# M2.net
KiCad netlist of a schematic drawn in EAGLE
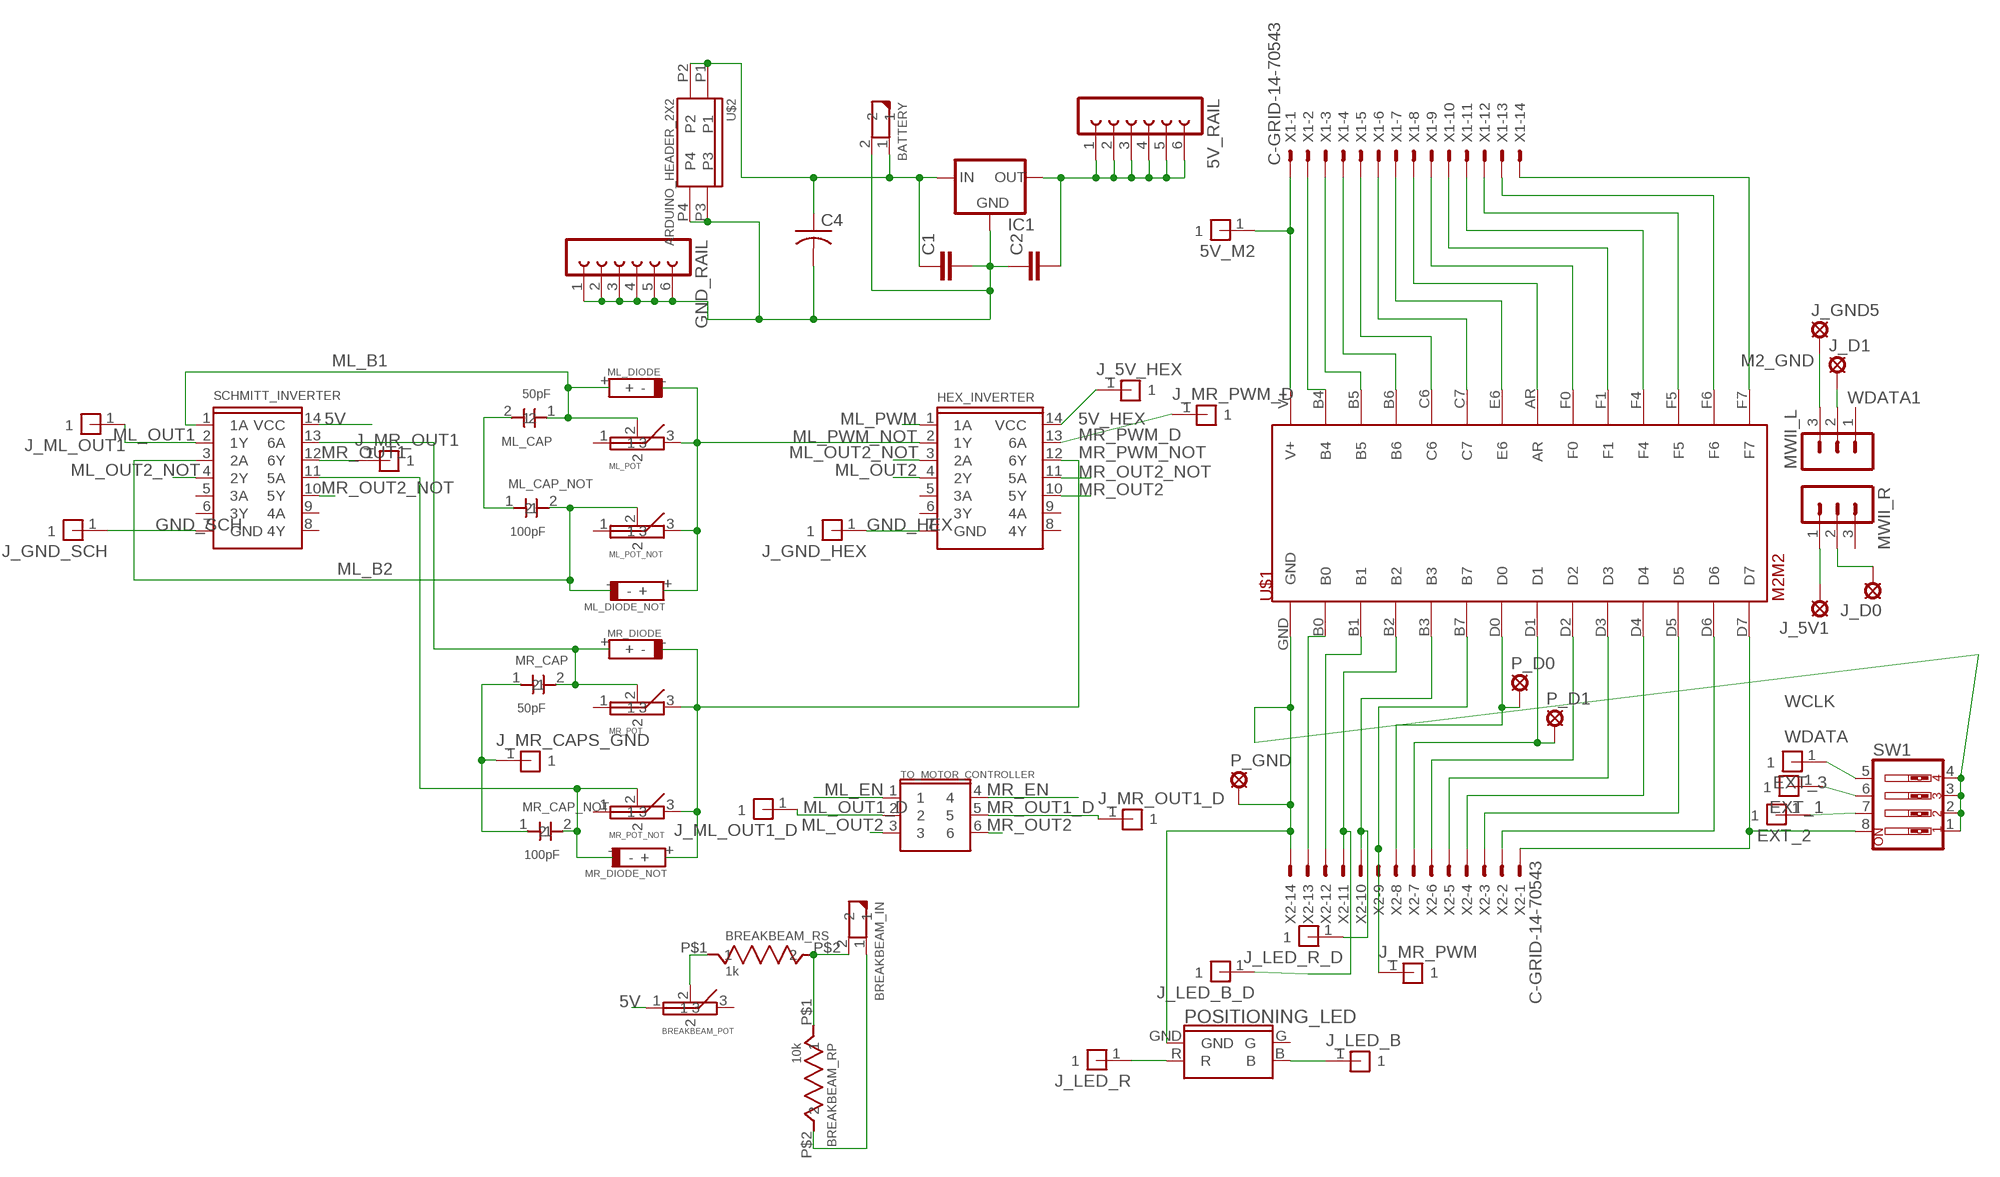
[diagram p0: schematic, sheet 1]

(export (version "E")
  (design (tool "Eeschema 10.0.6"))
  (components
    (comp (ref "5V_M2")
      (value "ARDUINO_HEADER_1X1_OCTAGON")
      (footprint "eagle-import:ARDUINO_HEADER_1X1_OCTAGON")
      (libsource (lib "eagle-import") (part "ARDUINO_HEADER_1X1_OCTAGON"))
    )
    (comp (ref "5V_RAIL")
      (value "FE06-1")
      (footprint "eagle-import:FE06")
      (libsource (lib "eagle-import") (part "FE06-1"))
    )
    (comp (ref "BATTERY")
      (value "MOLEX_2_PIN")
      (footprint "eagle-import:MOLEX_2_PIN")
      (libsource (lib "eagle-import") (part "MOLEX_2_PIN"))
    )
    (comp (ref "BREAKBEAM_IN")
      (value "MOLEX_2_PIN")
      (footprint "eagle-import:MOLEX_2_PIN")
      (libsource (lib "eagle-import") (part "MOLEX_2_PIN"))
    )
    (comp (ref "BREAKBEAM_POT")
      (value "POTENTIOMETER_1")
      (footprint "eagle-import:POTENTIOMETER_1")
      (libsource (lib "eagle-import") (part "POTENTIOMETER_1"))
    )
    (comp (ref "BREAKBEAM_RP")
      (value "10k")
      (footprint "eagle-import:RESISTOR_THROUGH_8MM")
      (libsource (lib "eagle-import") (part "RESISTOR_THROUGH_8MM"))
    )
    (comp (ref "BREAKBEAM_RS")
      (value "1k")
      (footprint "eagle-import:RESISTOR_THROUGH_8MM")
      (libsource (lib "eagle-import") (part "RESISTOR_THROUGH_8MM"))
    )
    (comp (ref "C1")
      (value "C2,5-3")
      (footprint "eagle-import:C2.5-3")
      (libsource (lib "eagle-import") (part "C2,5-3"))
    )
    (comp (ref "C2")
      (value "C2,5-3")
      (footprint "eagle-import:C2.5-3")
      (libsource (lib "eagle-import") (part "C2,5-3"))
    )
    (comp (ref "C4")
      (value "C-US050-025X075")
      (footprint "eagle-import:C050-025X075")
      (libsource (lib "eagle-import") (part "C-US050-025X075"))
    )
    (comp (ref "EXT_1")
      (value "ARDUINO_HEADER_1X1_OCTAGON")
      (footprint "eagle-import:ARDUINO_HEADER_1X1_OCTAGON")
      (libsource (lib "eagle-import") (part "ARDUINO_HEADER_1X1_OCTAGON"))
    )
    (comp (ref "EXT_2")
      (value "ARDUINO_HEADER_1X1_OCTAGON")
      (footprint "eagle-import:ARDUINO_HEADER_1X1_OCTAGON")
      (libsource (lib "eagle-import") (part "ARDUINO_HEADER_1X1_OCTAGON"))
    )
    (comp (ref "EXT_3")
      (value "ARDUINO_HEADER_1X1_OCTAGON")
      (footprint "eagle-import:ARDUINO_HEADER_1X1_OCTAGON")
      (libsource (lib "eagle-import") (part "ARDUINO_HEADER_1X1_OCTAGON"))
    )
    (comp (ref "GND_RAIL")
      (value "FE06-1")
      (footprint "eagle-import:FE06")
      (libsource (lib "eagle-import") (part "FE06-1"))
    )
    (comp (ref "HEX_INVERTER")
      (value "SN74HC04N_HEX_INVERTER")
      (footprint "eagle-import:DIP14")
      (libsource (lib "eagle-import") (part "SN74HC04N_HEX_INVERTER"))
    )
    (comp (ref "IC1")
      (value "78MXXS")
      (footprint "eagle-import:78MXXS")
      (libsource (lib "eagle-import") (part "78MXXS"))
    )
    (comp (ref "J_5V1")
      (value "LSP10")
      (footprint "eagle-import:LSP10")
      (libsource (lib "eagle-import") (part "LSP10"))
    )
    (comp (ref "J_5V_HEX")
      (value "ARDUINO_HEADER_1X1_OCTAGON")
      (footprint "eagle-import:ARDUINO_HEADER_1X1_OCTAGON")
      (libsource (lib "eagle-import") (part "ARDUINO_HEADER_1X1_OCTAGON"))
    )
    (comp (ref "J_D0")
      (value "LSP10")
      (footprint "eagle-import:LSP10")
      (libsource (lib "eagle-import") (part "LSP10"))
    )
    (comp (ref "J_D1")
      (value "LSP10")
      (footprint "eagle-import:LSP10")
      (libsource (lib "eagle-import") (part "LSP10"))
    )
    (comp (ref "J_GND5")
      (value "LSP10")
      (footprint "eagle-import:LSP10")
      (libsource (lib "eagle-import") (part "LSP10"))
    )
    (comp (ref "J_GND_HEX")
      (value "ARDUINO_HEADER_1X1_OCTAGON")
      (footprint "eagle-import:ARDUINO_HEADER_1X1_OCTAGON")
      (libsource (lib "eagle-import") (part "ARDUINO_HEADER_1X1_OCTAGON"))
    )
    (comp (ref "J_GND_SCH")
      (value "ARDUINO_HEADER_1X1_OCTAGON")
      (footprint "eagle-import:ARDUINO_HEADER_1X1_OCTAGON")
      (libsource (lib "eagle-import") (part "ARDUINO_HEADER_1X1_OCTAGON"))
    )
    (comp (ref "J_LED_B")
      (value "ARDUINO_HEADER_1X1_OCTAGON")
      (footprint "eagle-import:ARDUINO_HEADER_1X1_OCTAGON")
      (libsource (lib "eagle-import") (part "ARDUINO_HEADER_1X1_OCTAGON"))
    )
    (comp (ref "J_LED_B_D")
      (value "ARDUINO_HEADER_1X1_OCTAGON")
      (footprint "eagle-import:ARDUINO_HEADER_1X1_OCTAGON")
      (libsource (lib "eagle-import") (part "ARDUINO_HEADER_1X1_OCTAGON"))
    )
    (comp (ref "J_LED_R")
      (value "ARDUINO_HEADER_1X1_OCTAGON")
      (footprint "eagle-import:ARDUINO_HEADER_1X1_OCTAGON")
      (libsource (lib "eagle-import") (part "ARDUINO_HEADER_1X1_OCTAGON"))
    )
    (comp (ref "J_LED_R_D")
      (value "ARDUINO_HEADER_1X1_OCTAGON")
      (footprint "eagle-import:ARDUINO_HEADER_1X1_OCTAGON")
      (libsource (lib "eagle-import") (part "ARDUINO_HEADER_1X1_OCTAGON"))
    )
    (comp (ref "J_ML_OUT1")
      (value "ARDUINO_HEADER_1X1_OCTAGON")
      (footprint "eagle-import:ARDUINO_HEADER_1X1_OCTAGON")
      (libsource (lib "eagle-import") (part "ARDUINO_HEADER_1X1_OCTAGON"))
    )
    (comp (ref "J_ML_OUT1_D")
      (value "ARDUINO_HEADER_1X1_OCTAGON")
      (footprint "eagle-import:ARDUINO_HEADER_1X1_OCTAGON")
      (libsource (lib "eagle-import") (part "ARDUINO_HEADER_1X1_OCTAGON"))
    )
    (comp (ref "J_MR_CAPS_GND")
      (value "ARDUINO_HEADER_1X1_OCTAGON")
      (footprint "eagle-import:ARDUINO_HEADER_1X1_OCTAGON")
      (libsource (lib "eagle-import") (part "ARDUINO_HEADER_1X1_OCTAGON"))
    )
    (comp (ref "J_MR_OUT1")
      (value "ARDUINO_HEADER_1X1_OCTAGON")
      (footprint "eagle-import:ARDUINO_HEADER_1X1_OCTAGON")
      (libsource (lib "eagle-import") (part "ARDUINO_HEADER_1X1_OCTAGON"))
    )
    (comp (ref "J_MR_OUT1_D")
      (value "ARDUINO_HEADER_1X1_OCTAGON")
      (footprint "eagle-import:ARDUINO_HEADER_1X1_OCTAGON")
      (libsource (lib "eagle-import") (part "ARDUINO_HEADER_1X1_OCTAGON"))
    )
    (comp (ref "J_MR_PWM")
      (value "ARDUINO_HEADER_1X1_OCTAGON")
      (footprint "eagle-import:ARDUINO_HEADER_1X1_OCTAGON")
      (libsource (lib "eagle-import") (part "ARDUINO_HEADER_1X1_OCTAGON"))
    )
    (comp (ref "J_MR_PWM_D")
      (value "ARDUINO_HEADER_1X1_OCTAGON")
      (footprint "eagle-import:ARDUINO_HEADER_1X1_OCTAGON")
      (libsource (lib "eagle-import") (part "ARDUINO_HEADER_1X1_OCTAGON"))
    )
    (comp (ref "ML_CAP")
      (value "50pF")
      (footprint "eagle-import:CERAMIC_CAPACITOR")
      (libsource (lib "eagle-import") (part "CERAMIC_CAPACITOR"))
    )
    (comp (ref "ML_CAP_NOT")
      (value "100pF")
      (footprint "eagle-import:CERAMIC_CAPACITOR")
      (libsource (lib "eagle-import") (part "CERAMIC_CAPACITOR"))
    )
    (comp (ref "ML_DIODE")
      (value "1N914B")
      (footprint "eagle-import:1N914B")
      (libsource (lib "eagle-import") (part "1N914B"))
    )
    (comp (ref "ML_DIODE_NOT")
      (value "1N914B")
      (footprint "eagle-import:1N914B")
      (libsource (lib "eagle-import") (part "1N914B"))
    )
    (comp (ref "ML_POT")
      (value "POTENTIOMETER_1")
      (footprint "eagle-import:POTENTIOMETER_1")
      (libsource (lib "eagle-import") (part "POTENTIOMETER_1"))
    )
    (comp (ref "ML_POT_NOT")
      (value "POTENTIOMETER_1")
      (footprint "eagle-import:POTENTIOMETER_1")
      (libsource (lib "eagle-import") (part "POTENTIOMETER_1"))
    )
    (comp (ref "MR_CAP")
      (value "50pF")
      (footprint "eagle-import:CERAMIC_CAPACITOR")
      (libsource (lib "eagle-import") (part "CERAMIC_CAPACITOR"))
    )
    (comp (ref "MR_CAP_NOT")
      (value "100pF")
      (footprint "eagle-import:CERAMIC_CAPACITOR")
      (libsource (lib "eagle-import") (part "CERAMIC_CAPACITOR"))
    )
    (comp (ref "MR_DIODE")
      (value "1N914B")
      (footprint "eagle-import:1N914B")
      (libsource (lib "eagle-import") (part "1N914B"))
    )
    (comp (ref "MR_DIODE_NOT")
      (value "1N914B")
      (footprint "eagle-import:1N914B")
      (libsource (lib "eagle-import") (part "1N914B"))
    )
    (comp (ref "MR_POT")
      (value "POTENTIOMETER_1")
      (footprint "eagle-import:POTENTIOMETER_1")
      (libsource (lib "eagle-import") (part "POTENTIOMETER_1"))
    )
    (comp (ref "MR_POT_NOT")
      (value "POTENTIOMETER_1")
      (footprint "eagle-import:POTENTIOMETER_1")
      (libsource (lib "eagle-import") (part "POTENTIOMETER_1"))
    )
    (comp (ref "MWII_L")
      (value "MA03-1")
      (footprint "eagle-import:MA03-1")
      (libsource (lib "eagle-import") (part "MA03-1"))
    )
    (comp (ref "MWII_R")
      (value "MA03-1")
      (footprint "eagle-import:MA03-1")
      (libsource (lib "eagle-import") (part "MA03-1"))
    )
    (comp (ref "POSITIONING_LED")
      (value "RGB_LED")
      (footprint "eagle-import:RBG_LED")
      (libsource (lib "eagle-import") (part "RGB_LED"))
    )
    (comp (ref "P_D0")
      (value "LSP10")
      (footprint "eagle-import:LSP10")
      (libsource (lib "eagle-import") (part "LSP10"))
    )
    (comp (ref "P_D1")
      (value "LSP10")
      (footprint "eagle-import:LSP10")
      (libsource (lib "eagle-import") (part "LSP10"))
    )
    (comp (ref "P_GND")
      (value "LSP10")
      (footprint "eagle-import:LSP10")
      (libsource (lib "eagle-import") (part "LSP10"))
    )
    (comp (ref "SCHMITT_INVERTER")
      (value "SN74HC14N_SCHMITT_INVERTER")
      (footprint "eagle-import:DIP14")
      (libsource (lib "eagle-import") (part "SN74HC14N_SCHMITT_INVERTER"))
    )
    (comp (ref "SW1")
      (value "SW_DIP-4")
      (footprint "eagle-import:EDG-04")
      (libsource (lib "eagle-import") (part "SW_DIP-4"))
    )
    (comp (ref "TO_MOTOR_CONTROLLER")
      (value "ARDUINO_HEADER_3X2")
      (footprint "eagle-import:ARDUINO_HEADER_3X2")
      (libsource (lib "eagle-import") (part "ARDUINO_HEADER_3X2"))
    )
    (comp (ref "U$1")
      (value "M2M2")
      (footprint "eagle-import:M2")
      (libsource (lib "eagle-import") (part "M2M2"))
    )
    (comp (ref "U$2")
      (value "ARDUINO_HEADER_2X2")
      (footprint "eagle-import:ARDUINO_HEADER_2X2")
      (libsource (lib "eagle-import") (part "ARDUINO_HEADER_2X2"))
    )
    (comp (ref "X1")
      (value "C-GRID-14-70543")
      (footprint "eagle-import:70543-14")
      (libsource (lib "eagle-import") (part "C-GRID-14-70543"))
    )
    (comp (ref "X2")
      (value "C-GRID-14-70543")
      (footprint "eagle-import:70543-14")
      (libsource (lib "eagle-import") (part "C-GRID-14-70543"))
    )
  )
  (nets
    (net (code "1") (name "/5V") (class "Default")
      (node (ref "5V_RAIL") (pin "1") (pinfunction "1_1") (pintype "passive"))
      (node (ref "5V_RAIL") (pin "2") (pinfunction "2_2") (pintype "passive"))
      (node (ref "5V_RAIL") (pin "3") (pinfunction "3_3") (pintype "passive"))
      (node (ref "5V_RAIL") (pin "4") (pinfunction "4_4") (pintype "passive"))
      (node (ref "5V_RAIL") (pin "5") (pinfunction "5_5") (pintype "passive"))
      (node (ref "5V_RAIL") (pin "6") (pinfunction "6_6") (pintype "passive"))
      (node (ref "BREAKBEAM_POT") (pin "1") (pinfunction "1_1") (pintype "bidirectional"))
      (node (ref "C2") (pin "2") (pinfunction "2_2") (pintype "passive"))
      (node (ref "IC1") (pin "OUT") (pinfunction "OUT_OUT") (pintype "passive"))
      (node (ref "SCHMITT_INVERTER") (pin "14") (pinfunction "VCC_14") (pintype "bidirectional"))
    )
    (net (code "2") (name "/5V_HEX") (class "Default")
      (node (ref "HEX_INVERTER") (pin "14") (pinfunction "VCC_14") (pintype "bidirectional"))
      (node (ref "J_5V_HEX") (pin "1") (pinfunction "1_1") (pintype "bidirectional"))
    )
    (net (code "3") (name "/BREAKBEAM_OUT") (class "Default")
      (node (ref "BREAKBEAM_IN") (pin "2") (pinfunction "2_2") (pintype "bidirectional"))
      (node (ref "BREAKBEAM_RP") (pin "P$1") (pinfunction "1_P$1") (pintype "bidirectional"))
      (node (ref "BREAKBEAM_RS") (pin "P$2") (pinfunction "2_P$2") (pintype "bidirectional"))
      (node (ref "U$1") (pin "C6") (pinfunction "C6_C6") (pintype "bidirectional"))
      (node (ref "X1") (pin "5") (pinfunction "S_5") (pintype "passive"))
    )
    (net (code "4") (name "/GND_HEX") (class "Default")
      (node (ref "HEX_INVERTER") (pin "7") (pinfunction "GND_7") (pintype "bidirectional"))
      (node (ref "J_GND_HEX") (pin "1") (pinfunction "1_1") (pintype "bidirectional"))
    )
    (net (code "5") (name "/GND_SCH") (class "Default")
      (node (ref "J_GND_SCH") (pin "1") (pinfunction "1_1") (pintype "bidirectional"))
      (node (ref "SCHMITT_INVERTER") (pin "7") (pinfunction "GND_7") (pintype "bidirectional"))
    )
    (net (code "6") (name "/M2_GND") (class "Default")
      (node (ref "BREAKBEAM_IN") (pin "1") (pinfunction "1_1") (pintype "bidirectional"))
      (node (ref "BREAKBEAM_RP") (pin "P$2") (pinfunction "2_P$2") (pintype "bidirectional"))
      (node (ref "J_GND5") (pin "MP") (pinfunction "MP_MP") (pintype "passive"))
      (node (ref "MWII_L") (pin "3") (pinfunction "3_3") (pintype "passive"))
    )
    (net (code "7") (name "/ML_B1") (class "Default")
      (node (ref "ML_CAP") (pin "1") (pinfunction "1_1") (pintype "bidirectional"))
      (node (ref "ML_DIODE") (pin "+") (pinfunction "+_+") (pintype "input"))
      (node (ref "ML_POT") (pin "2") (pinfunction "2_2") (pintype "bidirectional"))
      (node (ref "SCHMITT_INVERTER") (pin "1") (pinfunction "1A_1") (pintype "bidirectional"))
    )
    (net (code "8") (name "/ML_B2") (class "Default")
      (node (ref "ML_CAP_NOT") (pin "2") (pinfunction "2_2") (pintype "bidirectional"))
      (node (ref "ML_DIODE_NOT") (pin "-") (pinfunction "-_-") (pintype "output"))
      (node (ref "ML_POT_NOT") (pin "2") (pinfunction "2_2") (pintype "bidirectional"))
      (node (ref "SCHMITT_INVERTER") (pin "3") (pinfunction "2A_3") (pintype "bidirectional"))
    )
    (net (code "9") (name "/ML_EN") (class "Default")
      (node (ref "TO_MOTOR_CONTROLLER") (pin "1") (pinfunction "1_1") (pintype "bidirectional"))
      (node (ref "U$1") (pin "B0") (pinfunction "B0_B0") (pintype "bidirectional"))
      (node (ref "X2") (pin "13") (pinfunction "S_13") (pintype "passive"))
    )
    (net (code "10") (name "/ML_OUT1") (class "Default")
      (node (ref "J_ML_OUT1") (pin "1") (pinfunction "1_1") (pintype "bidirectional"))
      (node (ref "SCHMITT_INVERTER") (pin "2") (pinfunction "1Y_2") (pintype "bidirectional"))
    )
    (net (code "11") (name "/ML_OUT1_D") (class "Default")
      (node (ref "J_ML_OUT1_D") (pin "1") (pinfunction "1_1") (pintype "bidirectional"))
      (node (ref "TO_MOTOR_CONTROLLER") (pin "2") (pinfunction "2_2") (pintype "bidirectional"))
    )
    (net (code "12") (name "/ML_OUT2") (class "Default")
      (node (ref "HEX_INVERTER") (pin "4") (pinfunction "2Y_4") (pintype "bidirectional"))
      (node (ref "TO_MOTOR_CONTROLLER") (pin "3") (pinfunction "3_3") (pintype "bidirectional"))
    )
    (net (code "13") (name "/ML_OUT2_NOT") (class "Default")
      (node (ref "HEX_INVERTER") (pin "3") (pinfunction "2A_3") (pintype "bidirectional"))
      (node (ref "SCHMITT_INVERTER") (pin "4") (pinfunction "2Y_4") (pintype "bidirectional"))
    )
    (net (code "14") (name "/ML_PWM") (class "Default")
      (node (ref "HEX_INVERTER") (pin "1") (pinfunction "1A_1") (pintype "bidirectional"))
      (node (ref "U$1") (pin "B6") (pinfunction "B6_B6") (pintype "bidirectional"))
      (node (ref "X1") (pin "4") (pinfunction "S_4") (pintype "passive"))
    )
    (net (code "15") (name "/ML_PWM_NOT") (class "Default")
      (node (ref "HEX_INVERTER") (pin "2") (pinfunction "1Y_2") (pintype "bidirectional"))
      (node (ref "ML_DIODE") (pin "-") (pinfunction "-_-") (pintype "output"))
      (node (ref "ML_DIODE_NOT") (pin "+") (pinfunction "+_+") (pintype "input"))
      (node (ref "ML_POT") (pin "3") (pinfunction "3_3") (pintype "bidirectional"))
      (node (ref "ML_POT_NOT") (pin "3") (pinfunction "3_3") (pintype "bidirectional"))
    )
    (net (code "16") (name "/MR_EN") (class "Default")
      (node (ref "TO_MOTOR_CONTROLLER") (pin "4") (pinfunction "4_4") (pintype "bidirectional"))
      (node (ref "U$1") (pin "B1") (pinfunction "B1_B1") (pintype "bidirectional"))
      (node (ref "X2") (pin "12") (pinfunction "S_12") (pintype "passive"))
    )
    (net (code "17") (name "/MR_OUT1") (class "Default")
      (node (ref "J_MR_OUT1") (pin "1") (pinfunction "1_1") (pintype "bidirectional"))
      (node (ref "SCHMITT_INVERTER") (pin "12") (pinfunction "6Y_12") (pintype "bidirectional"))
    )
    (net (code "18") (name "/MR_OUT1_D") (class "Default")
      (node (ref "J_MR_OUT1_D") (pin "1") (pinfunction "1_1") (pintype "bidirectional"))
      (node (ref "TO_MOTOR_CONTROLLER") (pin "5") (pinfunction "5_5") (pintype "bidirectional"))
    )
    (net (code "19") (name "/MR_OUT2") (class "Default")
      (node (ref "HEX_INVERTER") (pin "10") (pinfunction "5Y_10") (pintype "bidirectional"))
      (node (ref "TO_MOTOR_CONTROLLER") (pin "6") (pinfunction "6_6") (pintype "bidirectional"))
    )
    (net (code "20") (name "/MR_OUT2_NOT") (class "Default")
      (node (ref "HEX_INVERTER") (pin "11") (pinfunction "5A_11") (pintype "bidirectional"))
      (node (ref "SCHMITT_INVERTER") (pin "10") (pinfunction "5Y_10") (pintype "bidirectional"))
    )
    (net (code "21") (name "/MR_PWM_D") (class "Default")
      (node (ref "HEX_INVERTER") (pin "13") (pinfunction "6A_13") (pintype "bidirectional"))
      (node (ref "J_MR_PWM_D") (pin "1") (pinfunction "1_1") (pintype "bidirectional"))
    )
    (net (code "22") (name "/MR_PWM_NOT") (class "Default")
      (node (ref "HEX_INVERTER") (pin "12") (pinfunction "6Y_12") (pintype "bidirectional"))
      (node (ref "MR_DIODE") (pin "-") (pinfunction "-_-") (pintype "output"))
      (node (ref "MR_DIODE_NOT") (pin "+") (pinfunction "+_+") (pintype "input"))
      (node (ref "MR_POT") (pin "3") (pinfunction "3_3") (pintype "bidirectional"))
      (node (ref "MR_POT_NOT") (pin "3") (pinfunction "3_3") (pintype "bidirectional"))
    )
    (net (code "23") (name "/WCLK") (class "Default")
      (node (ref "P_D0") (pin "MP") (pinfunction "MP_MP") (pintype "passive"))
      (node (ref "U$1") (pin "D0") (pinfunction "D0_D0") (pintype "bidirectional"))
      (node (ref "X2") (pin "8") (pinfunction "S_8") (pintype "passive"))
    )
    (net (code "24") (name "/WDATA") (class "Default")
      (node (ref "P_D1") (pin "MP") (pinfunction "MP_MP") (pintype "passive"))
      (node (ref "U$1") (pin "D1") (pinfunction "D1_D1") (pintype "bidirectional"))
      (node (ref "X2") (pin "7") (pinfunction "S_7") (pintype "passive"))
    )
    (net (code "25") (name "/WDATA1") (class "Default")
      (node (ref "J_D1") (pin "MP") (pinfunction "MP_MP") (pintype "passive"))
      (node (ref "MWII_L") (pin "2") (pinfunction "2_2") (pintype "passive"))
    )
    (net (code "26") (name "Net-(BATTERY-Pad1)") (class "Default")
      (node (ref "BATTERY") (pin "1") (pinfunction "1_1") (pintype "bidirectional"))
      (node (ref "C1") (pin "1") (pinfunction "1_1") (pintype "passive"))
      (node (ref "C4") (pin "1") (pinfunction "1_1") (pintype "passive"))
      (node (ref "IC1") (pin "IN") (pinfunction "IN_IN") (pintype "input"))
      (node (ref "U$2") (pin "P1") (pinfunction "P1_P1") (pintype "bidirectional"))
      (node (ref "U$2") (pin "P2") (pinfunction "P2_P2") (pintype "bidirectional"))
    )
    (net (code "27") (name "Net-(BATTERY-Pad2)") (class "Default")
      (node (ref "BATTERY") (pin "2") (pinfunction "2_2") (pintype "bidirectional"))
      (node (ref "C1") (pin "2") (pinfunction "2_2") (pintype "passive"))
      (node (ref "C2") (pin "1") (pinfunction "1_1") (pintype "passive"))
      (node (ref "C4") (pin "2") (pinfunction "2_2") (pintype "passive"))
      (node (ref "GND_RAIL") (pin "1") (pinfunction "1_1") (pintype "passive"))
      (node (ref "GND_RAIL") (pin "2") (pinfunction "2_2") (pintype "passive"))
      (node (ref "GND_RAIL") (pin "3") (pinfunction "3_3") (pintype "passive"))
      (node (ref "GND_RAIL") (pin "4") (pinfunction "4_4") (pintype "passive"))
      (node (ref "GND_RAIL") (pin "5") (pinfunction "5_5") (pintype "passive"))
      (node (ref "GND_RAIL") (pin "6") (pinfunction "6_6") (pintype "passive"))
      (node (ref "IC1") (pin "GND") (pinfunction "GND_GND") (pintype "input"))
      (node (ref "U$2") (pin "P3") (pinfunction "P3_P3") (pintype "bidirectional"))
      (node (ref "U$2") (pin "P4") (pinfunction "P4_P4") (pintype "bidirectional"))
    )
    (net (code "28") (name "Net-(BREAKBEAM_RS-1)") (class "Default")
      (node (ref "BREAKBEAM_POT") (pin "2") (pinfunction "2_2") (pintype "bidirectional"))
      (node (ref "BREAKBEAM_RS") (pin "P$1") (pinfunction "1_P$1") (pintype "bidirectional"))
    )
    (net (code "29") (name "Net-(EXT_1-Pad1)") (class "Default")
      (node (ref "EXT_1") (pin "1") (pinfunction "1_1") (pintype "bidirectional"))
      (node (ref "SW1") (pin "6") (pinfunction "6_6") (pintype "passive"))
    )
    (net (code "30") (name "Net-(EXT_2-Pad1)") (class "Default")
      (node (ref "EXT_2") (pin "1") (pinfunction "1_1") (pintype "bidirectional"))
      (node (ref "SW1") (pin "7") (pinfunction "7_7") (pintype "passive"))
    )
    (net (code "31") (name "Net-(EXT_3-Pad1)") (class "Default")
      (node (ref "EXT_3") (pin "1") (pinfunction "1_1") (pintype "bidirectional"))
      (node (ref "SW1") (pin "5") (pinfunction "5_5") (pintype "passive"))
    )
    (net (code "32") (name "Net-(J_5V1-PadMP)") (class "Default")
      (node (ref "J_5V1") (pin "MP") (pinfunction "MP_MP") (pintype "passive"))
      (node (ref "MWII_R") (pin "1") (pinfunction "1_1") (pintype "passive"))
    )
    (net (code "33") (name "Net-(J_D0-PadMP)") (class "Default")
      (node (ref "J_D0") (pin "MP") (pinfunction "MP_MP") (pintype "passive"))
      (node (ref "MWII_R") (pin "2") (pinfunction "2_2") (pintype "passive"))
    )
    (net (code "34") (name "Net-(J_LED_B-Pad1)") (class "Default")
      (node (ref "J_LED_B") (pin "1") (pinfunction "1_1") (pintype "bidirectional"))
      (node (ref "POSITIONING_LED") (pin "B") (pinfunction "B_B") (pintype "bidirectional"))
    )
    (net (code "35") (name "Net-(J_LED_R-Pad1)") (class "Default")
      (node (ref "J_LED_R") (pin "1") (pinfunction "1_1") (pintype "bidirectional"))
      (node (ref "POSITIONING_LED") (pin "R") (pinfunction "R_R") (pintype "bidirectional"))
    )
    (net (code "36") (name "Net-(J_MR_CAPS_GND-Pad1)") (class "Default")
      (node (ref "J_MR_CAPS_GND") (pin "1") (pinfunction "1_1") (pintype "bidirectional"))
      (node (ref "MR_CAP") (pin "1") (pinfunction "1_1") (pintype "bidirectional"))
      (node (ref "MR_CAP_NOT") (pin "1") (pinfunction "1_1") (pintype "bidirectional"))
    )
    (net (code "37") (name "Net-(ML_CAP-Pad2)") (class "Default")
      (node (ref "ML_CAP") (pin "2") (pinfunction "2_2") (pintype "bidirectional"))
      (node (ref "ML_CAP_NOT") (pin "1") (pinfunction "1_1") (pintype "bidirectional"))
    )
    (net (code "38") (name "Net-(SCHMITT_INVERTER-5A)") (class "Default")
      (node (ref "MR_CAP_NOT") (pin "2") (pinfunction "2_2") (pintype "bidirectional"))
      (node (ref "MR_DIODE_NOT") (pin "-") (pinfunction "-_-") (pintype "output"))
      (node (ref "MR_POT_NOT") (pin "2") (pinfunction "2_2") (pintype "bidirectional"))
      (node (ref "SCHMITT_INVERTER") (pin "11") (pinfunction "5A_11") (pintype "bidirectional"))
    )
    (net (code "39") (name "Net-(SCHMITT_INVERTER-6A)") (class "Default")
      (node (ref "MR_CAP") (pin "2") (pinfunction "2_2") (pintype "bidirectional"))
      (node (ref "MR_DIODE") (pin "+") (pinfunction "+_+") (pintype "input"))
      (node (ref "MR_POT") (pin "2") (pinfunction "2_2") (pintype "bidirectional"))
      (node (ref "SCHMITT_INVERTER") (pin "13") (pinfunction "6A_13") (pintype "bidirectional"))
    )
    (net (code "40") (name "Net-(X1A-S)") (class "Default")
      (node (ref "5V_M2") (pin "1") (pinfunction "1_1") (pintype "bidirectional"))
      (node (ref "U$1") (pin "V+") (pinfunction "V+_V+") (pintype "bidirectional"))
      (node (ref "X1") (pin "1") (pinfunction "S_1") (pintype "passive"))
    )
    (net (code "41") (name "Net-(X1B-S)") (class "Default")
      (node (ref "U$1") (pin "F1") (pinfunction "F1_F1") (pintype "bidirectional"))
      (node (ref "X1") (pin "10") (pinfunction "S_10") (pintype "passive"))
    )
    (net (code "42") (name "Net-(X1C-S)") (class "Default")
      (node (ref "U$1") (pin "F4") (pinfunction "F4_F4") (pintype "bidirectional"))
      (node (ref "X1") (pin "11") (pinfunction "S_11") (pintype "passive"))
    )
    (net (code "43") (name "Net-(X1D-S)") (class "Default")
      (node (ref "U$1") (pin "F5") (pinfunction "F5_F5") (pintype "bidirectional"))
      (node (ref "X1") (pin "12") (pinfunction "S_12") (pintype "passive"))
    )
    (net (code "44") (name "Net-(X1E-S)") (class "Default")
      (node (ref "U$1") (pin "F6") (pinfunction "F6_F6") (pintype "bidirectional"))
      (node (ref "X1") (pin "13") (pinfunction "S_13") (pintype "passive"))
    )
    (net (code "45") (name "Net-(X1F-S)") (class "Default")
      (node (ref "U$1") (pin "F7") (pinfunction "F7_F7") (pintype "bidirectional"))
      (node (ref "X1") (pin "14") (pinfunction "S_14") (pintype "passive"))
    )
    (net (code "46") (name "Net-(X1G-S)") (class "Default")
      (node (ref "U$1") (pin "B4") (pinfunction "B4_B4") (pintype "bidirectional"))
      (node (ref "X1") (pin "2") (pinfunction "S_2") (pintype "passive"))
    )
    (net (code "47") (name "Net-(X1H-S)") (class "Default")
      (node (ref "U$1") (pin "B5") (pinfunction "B5_B5") (pintype "bidirectional"))
      (node (ref "X1") (pin "3") (pinfunction "S_3") (pintype "passive"))
    )
    (net (code "48") (name "Net-(X1K-S)") (class "Default")
      (node (ref "U$1") (pin "C7") (pinfunction "C7_C7") (pintype "bidirectional"))
      (node (ref "X1") (pin "6") (pinfunction "S_6") (pintype "passive"))
    )
    (net (code "49") (name "Net-(X1L-S)") (class "Default")
      (node (ref "U$1") (pin "E6") (pinfunction "E6_E6") (pintype "bidirectional"))
      (node (ref "X1") (pin "7") (pinfunction "S_7") (pintype "passive"))
    )
    (net (code "50") (name "Net-(X1M-S)") (class "Default")
      (node (ref "U$1") (pin "AR") (pinfunction "AR_AR") (pintype "bidirectional"))
      (node (ref "X1") (pin "8") (pinfunction "S_8") (pintype "passive"))
    )
    (net (code "51") (name "Net-(X1N-S)") (class "Default")
      (node (ref "U$1") (pin "F0") (pinfunction "F0_F0") (pintype "bidirectional"))
      (node (ref "X1") (pin "9") (pinfunction "S_9") (pintype "passive"))
    )
    (net (code "52") (name "Net-(X2A-S)") (class "Default")
      (node (ref "SW1") (pin "8") (pinfunction "8_8") (pintype "passive"))
      (node (ref "U$1") (pin "D7") (pinfunction "D7_D7") (pintype "bidirectional"))
      (node (ref "X2") (pin "1") (pinfunction "S_1") (pintype "passive"))
    )
    (net (code "53") (name "Net-(X2B-S)") (class "Default")
      (node (ref "J_LED_R_D") (pin "1") (pinfunction "1_1") (pintype "bidirectional"))
      (node (ref "U$1") (pin "B3") (pinfunction "B3_B3") (pintype "bidirectional"))
      (node (ref "X2") (pin "10") (pinfunction "S_10") (pintype "passive"))
    )
    (net (code "54") (name "Net-(X2C-S)") (class "Default")
      (node (ref "J_LED_B_D") (pin "1") (pinfunction "1_1") (pintype "bidirectional"))
      (node (ref "U$1") (pin "B2") (pinfunction "B2_B2") (pintype "bidirectional"))
      (node (ref "X2") (pin "11") (pinfunction "S_11") (pintype "passive"))
    )
    (net (code "55") (name "Net-(X2F-S)") (class "Default")
      (node (ref "POSITIONING_LED") (pin "GND") (pinfunction "GND_GND") (pintype "bidirectional"))
      (node (ref "P_GND") (pin "MP") (pinfunction "MP_MP") (pintype "passive"))
      (node (ref "SW1") (pin "1") (pinfunction "1_1") (pintype "passive"))
      (node (ref "SW1") (pin "2") (pinfunction "2_2") (pintype "passive"))
      (node (ref "SW1") (pin "3") (pinfunction "3_3") (pintype "passive"))
      (node (ref "SW1") (pin "4") (pinfunction "4_4") (pintype "passive"))
      (node (ref "U$1") (pin "GND") (pinfunction "GND_GND") (pintype "bidirectional"))
      (node (ref "X2") (pin "14") (pinfunction "S_14") (pintype "passive"))
    )
    (net (code "56") (name "Net-(X2G-S)") (class "Default")
      (node (ref "U$1") (pin "D6") (pinfunction "D6_D6") (pintype "bidirectional"))
      (node (ref "X2") (pin "2") (pinfunction "S_2") (pintype "passive"))
    )
    (net (code "57") (name "Net-(X2H-S)") (class "Default")
      (node (ref "U$1") (pin "D5") (pinfunction "D5_D5") (pintype "bidirectional"))
      (node (ref "X2") (pin "3") (pinfunction "S_3") (pintype "passive"))
    )
    (net (code "58") (name "Net-(X2I-S)") (class "Default")
      (node (ref "U$1") (pin "D4") (pinfunction "D4_D4") (pintype "bidirectional"))
      (node (ref "X2") (pin "4") (pinfunction "S_4") (pintype "passive"))
    )
    (net (code "59") (name "Net-(X2J-S)") (class "Default")
      (node (ref "U$1") (pin "D3") (pinfunction "D3_D3") (pintype "bidirectional"))
      (node (ref "X2") (pin "5") (pinfunction "S_5") (pintype "passive"))
    )
    (net (code "60") (name "Net-(X2K-S)") (class "Default")
      (node (ref "U$1") (pin "D2") (pinfunction "D2_D2") (pintype "bidirectional"))
      (node (ref "X2") (pin "6") (pinfunction "S_6") (pintype "passive"))
    )
    (net (code "61") (name "Net-(X2N-S)") (class "Default")
      (node (ref "J_MR_PWM") (pin "1") (pinfunction "1_1") (pintype "bidirectional"))
      (node (ref "U$1") (pin "B7") (pinfunction "B7_B7") (pintype "bidirectional"))
      (node (ref "X2") (pin "9") (pinfunction "S_9") (pintype "passive"))
    )
    (net (code "62") (name "unconnected-(BREAKBEAM_POT-Pad3)") (class "Default")
      (node (ref "BREAKBEAM_POT") (pin "3") (pinfunction "3_3") (pintype "bidirectional"))
    )
    (net (code "63") (name "unconnected-(HEX_INVERTER-3A-Pad5)") (class "Default")
      (node (ref "HEX_INVERTER") (pin "5") (pinfunction "3A_5") (pintype "bidirectional"))
    )
    (net (code "64") (name "unconnected-(HEX_INVERTER-3Y-Pad6)") (class "Default")
      (node (ref "HEX_INVERTER") (pin "6") (pinfunction "3Y_6") (pintype "bidirectional"))
    )
    (net (code "65") (name "unconnected-(HEX_INVERTER-4A-Pad9)") (class "Default")
      (node (ref "HEX_INVERTER") (pin "9") (pinfunction "4A_9") (pintype "bidirectional"))
    )
    (net (code "66") (name "unconnected-(HEX_INVERTER-4Y-Pad8)") (class "Default")
      (node (ref "HEX_INVERTER") (pin "8") (pinfunction "4Y_8") (pintype "bidirectional"))
    )
    (net (code "67") (name "unconnected-(ML_POT-Pad1)") (class "Default")
      (node (ref "ML_POT") (pin "1") (pinfunction "1_1") (pintype "bidirectional"))
    )
    (net (code "68") (name "unconnected-(ML_POT_NOT-Pad1)") (class "Default")
      (node (ref "ML_POT_NOT") (pin "1") (pinfunction "1_1") (pintype "bidirectional"))
    )
    (net (code "69") (name "unconnected-(MR_POT-Pad1)") (class "Default")
      (node (ref "MR_POT") (pin "1") (pinfunction "1_1") (pintype "bidirectional"))
    )
    (net (code "70") (name "unconnected-(MR_POT_NOT-Pad1)") (class "Default")
      (node (ref "MR_POT_NOT") (pin "1") (pinfunction "1_1") (pintype "bidirectional"))
    )
    (net (code "71") (name "unconnected-(MWII_L-Pad1)") (class "Default")
      (node (ref "MWII_L") (pin "1") (pinfunction "1_1") (pintype "passive"))
    )
    (net (code "72") (name "unconnected-(MWII_R-Pad3)") (class "Default")
      (node (ref "MWII_R") (pin "3") (pinfunction "3_3") (pintype "passive"))
    )
    (net (code "73") (name "unconnected-(POSITIONING_LED-PadG)") (class "Default")
      (node (ref "POSITIONING_LED") (pin "G") (pinfunction "G_G") (pintype "bidirectional"))
    )
    (net (code "74") (name "unconnected-(SCHMITT_INVERTER-3A-Pad5)") (class "Default")
      (node (ref "SCHMITT_INVERTER") (pin "5") (pinfunction "3A_5") (pintype "bidirectional"))
    )
    (net (code "75") (name "unconnected-(SCHMITT_INVERTER-3Y-Pad6)") (class "Default")
      (node (ref "SCHMITT_INVERTER") (pin "6") (pinfunction "3Y_6") (pintype "bidirectional"))
    )
    (net (code "76") (name "unconnected-(SCHMITT_INVERTER-4A-Pad9)") (class "Default")
      (node (ref "SCHMITT_INVERTER") (pin "9") (pinfunction "4A_9") (pintype "bidirectional"))
    )
    (net (code "77") (name "unconnected-(SCHMITT_INVERTER-4Y-Pad8)") (class "Default")
      (node (ref "SCHMITT_INVERTER") (pin "8") (pinfunction "4Y_8") (pintype "bidirectional"))
    )
  )
)
